# SubNodeMainBoard.net
KiCad netlist of a schematic drawn in Altium Designer
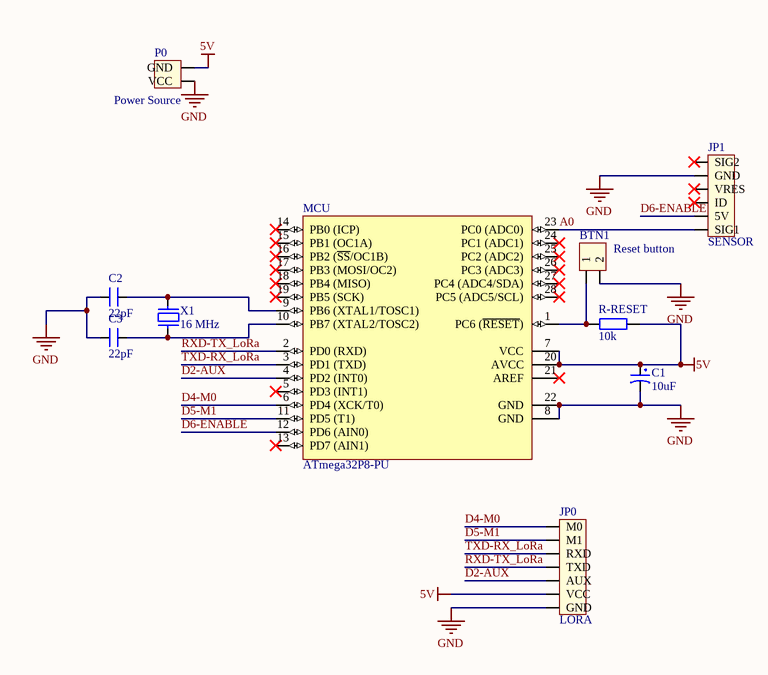
[diagram p0: SubNodeMainBoard.SchDoc]

(export (version "E")
  (design (tool "Eeschema 10.0.6"))
  (components
    (comp (ref "BTN1")
      (value "Reset button")
      (footprint "HED2")
      (description "Header 2 (Green)")
      (libsource (lib "") (part "Hed2_1"))
    )
    (comp (ref "C1")
      (value "10uF")
      (footprint "CP1/2")
      (description "Cap P  0,1uF < 22uF , 16 - 50V")
      (libsource (lib "syhaunguyen") (part "CP1"))
    )
    (comp (ref "C2")
      (value "22pF")
      (footprint "CN1")
      (description "Cap np  1pF - 472pF")
      (libsource (lib "syhaunguyen") (part "CN1"))
    )
    (comp (ref "C3")
      (value "22pF")
      (footprint "CN1")
      (description "Cap np  1pF - 472pF")
      (libsource (lib "syhaunguyen") (part "CN1"))
    )
    (comp (ref "JP0")
      (value "LORA")
      (footprint "CON7")
      (description "Connector 7")
      (libsource (lib "syhaunguyen") (part "Con7"))
    )
    (comp (ref "JP1")
      (value "SENSOR")
      (footprint "CON6")
      (description "Connector 6")
      (libsource (lib "syhaunguyen") (part "Con6"))
    )
    (comp (ref "MCU")
      (value "ATmega32P8-PU")
      (footprint "DIP28/W0.3")
      (description "8-Bit AVR Microcontroller with 8K Bytes of In-System Programmable Flash Memory")
      (libsource (lib "syhaunguyen") (part "ATmega8-L"))
    )
    (comp (ref "P0")
      (value "Power Source")
      (footprint "HED2")
      (description "Header 2 (Green)")
      (libsource (lib "syhaunguyen") (part "Hed2"))
    )
    (comp (ref "R-RESET")
      (value "10k")
      (footprint "R1/4W")
      (description "Resistor 1/4W")
      (libsource (lib "syhaunguyen") (part "R1/4W"))
    )
    (comp (ref "X1")
      (value "16 MHz")
      (footprint "XT2")
      (description "Crystal For all Crystal 2pin.")
      (libsource (lib "syhaunguyen") (part "XT2"))
    )
  )
  (nets
    (net (code "1") (name "/A0") (class "Default")
      (node (ref "JP1") (pin "6") (pinfunction "SIG1_6") (pintype "passive"))
      (node (ref "MCU") (pin "23") (pinfunction "PC0_(ADC0)_23") (pintype "bidirectional"))
    )
    (net (code "2") (name "/D2-AUX") (class "Default")
      (node (ref "JP0") (pin "5") (pinfunction "AUX_5") (pintype "passive"))
      (node (ref "MCU") (pin "4") (pinfunction "PD2_(INT0)_4") (pintype "bidirectional"))
    )
    (net (code "3") (name "/D4-M0") (class "Default")
      (node (ref "JP0") (pin "1") (pinfunction "M0_1") (pintype "passive"))
      (node (ref "MCU") (pin "6") (pinfunction "PD4_(XCK/T0)_6") (pintype "bidirectional"))
    )
    (net (code "4") (name "/D5-M1") (class "Default")
      (node (ref "JP0") (pin "2") (pinfunction "M1_2") (pintype "passive"))
      (node (ref "MCU") (pin "11") (pinfunction "PD5_(T1)_11") (pintype "bidirectional"))
    )
    (net (code "5") (name "/D6-ENABLE") (class "Default")
      (node (ref "JP1") (pin "5") (pinfunction "5V_5") (pintype "passive"))
      (node (ref "MCU") (pin "12") (pinfunction "PD6_(AIN0)_12") (pintype "bidirectional"))
    )
    (net (code "6") (name "/RXD-TX_LoRa") (class "Default")
      (node (ref "JP0") (pin "4") (pinfunction "TXD_4") (pintype "passive"))
      (node (ref "MCU") (pin "2") (pinfunction "PD0_(RXD)_2") (pintype "bidirectional"))
    )
    (net (code "7") (name "/TXD-RX_LoRa") (class "Default")
      (node (ref "JP0") (pin "3") (pinfunction "RXD_3") (pintype "passive"))
      (node (ref "MCU") (pin "3") (pinfunction "PD1_(TXD)_3") (pintype "bidirectional"))
    )
    (net (code "8") (name "5V") (class "Default")
      (node (ref "C1") (pin "1") (pinfunction "1_1") (pintype "passive"))
      (node (ref "JP0") (pin "6") (pinfunction "VCC_6") (pintype "passive"))
      (node (ref "MCU") (pin "20") (pinfunction "AVCC_20") (pintype "power_in"))
      (node (ref "MCU") (pin "7") (pinfunction "VCC_7") (pintype "power_in"))
      (node (ref "P0") (pin "2") (pinfunction "GND_2") (pintype "passive"))
      (node (ref "R-RESET") (pin "2") (pinfunction "2_2") (pintype "passive"))
    )
    (net (code "9") (name "GND") (class "Default")
      (node (ref "BTN1") (pin "2") (pinfunction "2_2") (pintype "passive"))
      (node (ref "C1") (pin "2") (pinfunction "2_2") (pintype "passive"))
      (node (ref "C2") (pin "1") (pinfunction "1_1") (pintype "passive"))
      (node (ref "C3") (pin "1") (pinfunction "1_1") (pintype "passive"))
      (node (ref "JP0") (pin "7") (pinfunction "GND_7") (pintype "passive"))
      (node (ref "JP1") (pin "2") (pinfunction "GND_2") (pintype "passive"))
      (node (ref "MCU") (pin "22") (pinfunction "GND_22") (pintype "power_in"))
      (node (ref "MCU") (pin "8") (pinfunction "GND_8") (pintype "power_in"))
      (node (ref "P0") (pin "1") (pinfunction "VCC_1") (pintype "passive"))
    )
    (net (code "10") (name "Net-(MCU-PB6_(XTAL1{slash}TOSC1))") (class "Default")
      (node (ref "C2") (pin "2") (pinfunction "2_2") (pintype "passive"))
      (node (ref "MCU") (pin "9") (pinfunction "PB6_(XTAL1/TOSC1)_9") (pintype "bidirectional"))
      (node (ref "X1") (pin "2") (pinfunction "2_2") (pintype "passive"))
    )
    (net (code "11") (name "Net-(MCU-PB7_(XTAL2{slash}TOSC2))") (class "Default")
      (node (ref "C3") (pin "2") (pinfunction "2_2") (pintype "passive"))
      (node (ref "MCU") (pin "10") (pinfunction "PB7_(XTAL2/TOSC2)_10") (pintype "bidirectional"))
      (node (ref "X1") (pin "1") (pinfunction "1_1") (pintype "passive"))
    )
    (net (code "12") (name "Net-(MCU-PC6_(~{RESET}))") (class "Default")
      (node (ref "BTN1") (pin "1") (pinfunction "1_1") (pintype "passive"))
      (node (ref "MCU") (pin "1") (pinfunction "PC6_(~{RESET})_1") (pintype "bidirectional"))
      (node (ref "R-RESET") (pin "1") (pinfunction "1_1") (pintype "passive"))
    )
    (net (code "13") (name "unconnected-(JP1-ID-Pad4)") (class "Default")
      (node (ref "JP1") (pin "4") (pinfunction "ID_4") (pintype "passive+no_connect"))
    )
    (net (code "14") (name "unconnected-(JP1-SIG2-Pad1)") (class "Default")
      (node (ref "JP1") (pin "1") (pinfunction "SIG2_1") (pintype "passive+no_connect"))
    )
    (net (code "15") (name "unconnected-(JP1-VRES-Pad3)") (class "Default")
      (node (ref "JP1") (pin "3") (pinfunction "VRES_3") (pintype "passive+no_connect"))
    )
    (net (code "16") (name "unconnected-(MCU-AREF-Pad21)") (class "Default")
      (node (ref "MCU") (pin "21") (pinfunction "AREF_21") (pintype "passive+no_connect"))
    )
    (net (code "17") (name "unconnected-(MCU-PB0_(ICP)-Pad14)") (class "Default")
      (node (ref "MCU") (pin "14") (pinfunction "PB0_(ICP)_14") (pintype "bidirectional+no_connect"))
    )
    (net (code "18") (name "unconnected-(MCU-PB1_(OC1A)-Pad15)") (class "Default")
      (node (ref "MCU") (pin "15") (pinfunction "PB1_(OC1A)_15") (pintype "bidirectional+no_connect"))
    )
    (net (code "19") (name "unconnected-(MCU-PB2_(~{SS}{slash}OC1B)-Pad16)") (class "Default")
      (node (ref "MCU") (pin "16") (pinfunction "PB2_(~{SS}/OC1B)_16") (pintype "bidirectional+no_connect"))
    )
    (net (code "20") (name "unconnected-(MCU-PB3_(MOSI{slash}OC2)-Pad17)") (class "Default")
      (node (ref "MCU") (pin "17") (pinfunction "PB3_(MOSI/OC2)_17") (pintype "bidirectional+no_connect"))
    )
    (net (code "21") (name "unconnected-(MCU-PB4_(MISO)-Pad18)") (class "Default")
      (node (ref "MCU") (pin "18") (pinfunction "PB4_(MISO)_18") (pintype "bidirectional+no_connect"))
    )
    (net (code "22") (name "unconnected-(MCU-PB5_(SCK)-Pad19)") (class "Default")
      (node (ref "MCU") (pin "19") (pinfunction "PB5_(SCK)_19") (pintype "bidirectional+no_connect"))
    )
    (net (code "23") (name "unconnected-(MCU-PC1_(ADC1)-Pad24)") (class "Default")
      (node (ref "MCU") (pin "24") (pinfunction "PC1_(ADC1)_24") (pintype "bidirectional+no_connect"))
    )
    (net (code "24") (name "unconnected-(MCU-PC2_(ADC2)-Pad25)") (class "Default")
      (node (ref "MCU") (pin "25") (pinfunction "PC2_(ADC2)_25") (pintype "bidirectional+no_connect"))
    )
    (net (code "25") (name "unconnected-(MCU-PC3_(ADC3)-Pad26)") (class "Default")
      (node (ref "MCU") (pin "26") (pinfunction "PC3_(ADC3)_26") (pintype "bidirectional+no_connect"))
    )
    (net (code "26") (name "unconnected-(MCU-PC4_(ADC4{slash}SDA)-Pad27)") (class "Default")
      (node (ref "MCU") (pin "27") (pinfunction "PC4_(ADC4/SDA)_27") (pintype "bidirectional+no_connect"))
    )
    (net (code "27") (name "unconnected-(MCU-PC5_(ADC5{slash}SCL)-Pad28)") (class "Default")
      (node (ref "MCU") (pin "28") (pinfunction "PC5_(ADC5/SCL)_28") (pintype "bidirectional+no_connect"))
    )
    (net (code "28") (name "unconnected-(MCU-PD3_(INT1)-Pad5)") (class "Default")
      (node (ref "MCU") (pin "5") (pinfunction "PD3_(INT1)_5") (pintype "bidirectional+no_connect"))
    )
    (net (code "29") (name "unconnected-(MCU-PD7_(AIN1)-Pad13)") (class "Default")
      (node (ref "MCU") (pin "13") (pinfunction "PD7_(AIN1)_13") (pintype "bidirectional+no_connect"))
    )
  )
)
